# EVK-IRIS-W1-PowerSchDoc.net
KiCad netlist of a schematic drawn in Altium Designer
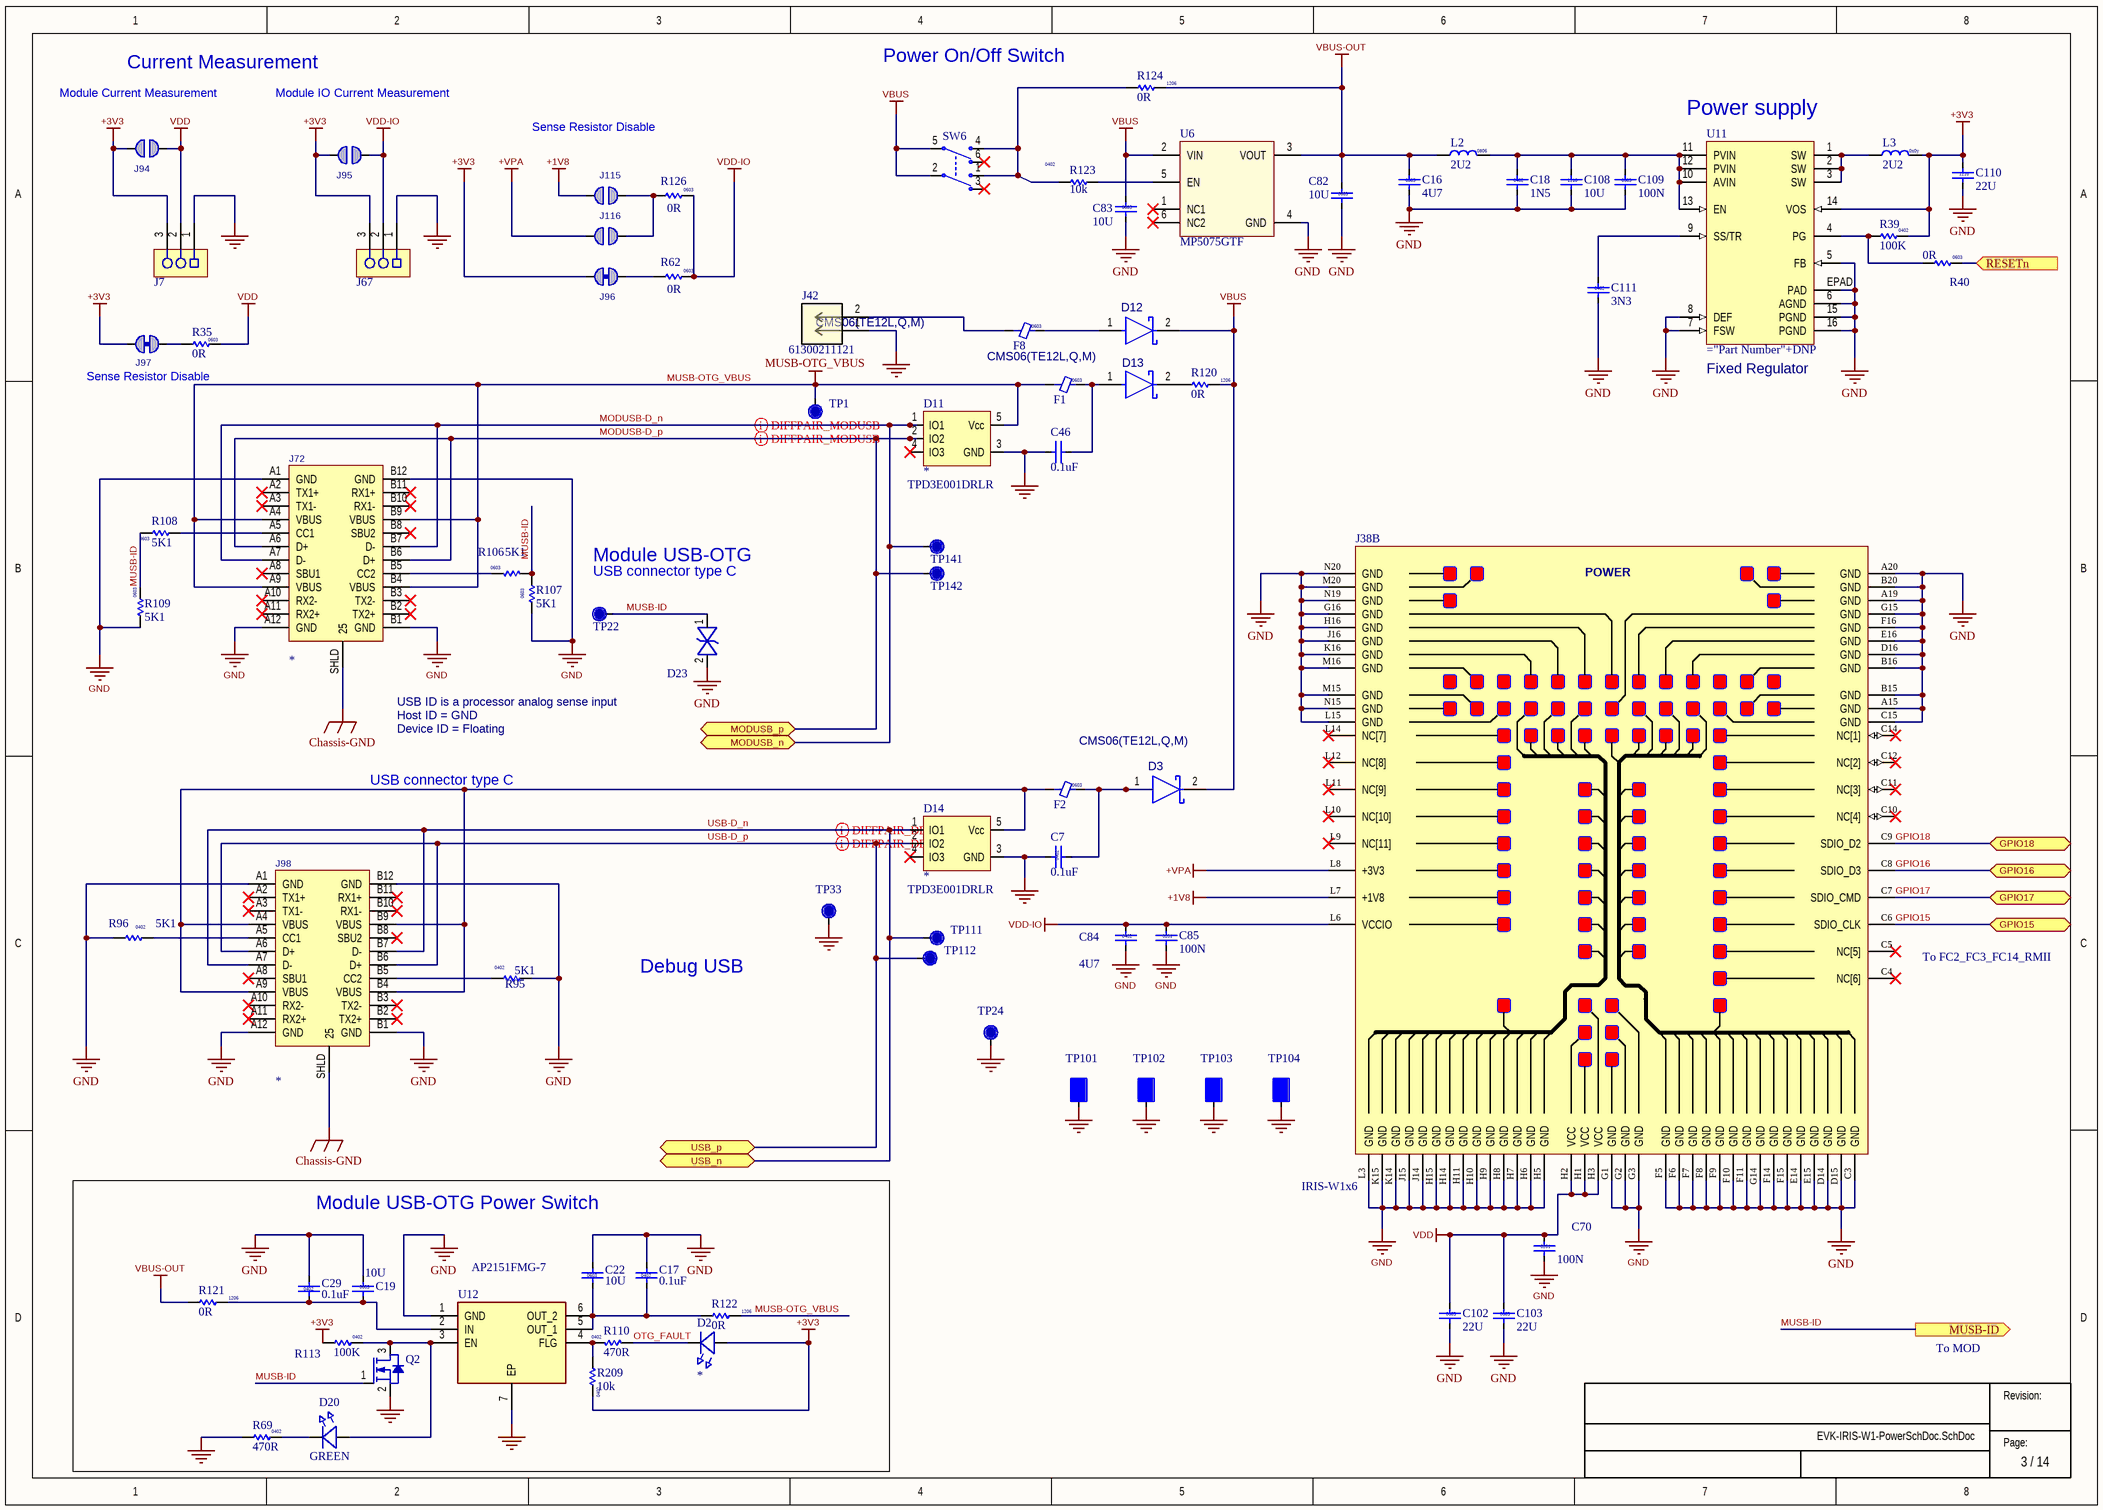
[diagram p0: EVK-IRIS-W1-PowerSchDoc.SchDoc]

(export (version "E")
  (design (tool "Eeschema 10.0.6"))
  (components
    (comp (ref "C7")
      (value "0.1uF")
      (footprint "Cap 0402 HD")
      (description "Cap, Ceramic 0.1uF 10V 10% X5R 0402")
      (fields
        (field (name "SIZE") "0402")
        (field (name "PART NUMBER") "120-00016")
        (field (name "TOLERANCE") "+/- 10%")
      )
      (libsource (lib "Arena_Parts_DB_Lib") (part "Cap Chip"))
    )
    (comp (ref "C16")
      (value "4U7")
      (footprint "Cap 0805")
      (description "CAP CER X5R 0805 4U7 10% 25V")
      (fields
        (field (name "SIZE") "0805")
        (field (name "PART NUMBER") "UBXH01-0000007")
        (field (name "TOLERANCE") "10%")
      )
      (libsource (lib "UBX_Parts_DB_Lib") (part "Cap Chip"))
    )
    (comp (ref "C17")
      (value "0.1uF")
      (footprint "Cap 0402 HD")
      (description "Cap, Ceramic 0.1uF 10V 10% X5R 0402")
      (fields
        (field (name "SIZE") "0402")
        (field (name "PART NUMBER") "120-00016")
        (field (name "TOLERANCE") "+/- 10%")
      )
      (libsource (lib "Arena_Parts_DB_Lib") (part "Cap Chip"))
    )
    (comp (ref "C18")
      (value "1N5")
      (footprint "CAP 0402")
      (description "CAP CER X7R 0402 1N5 10% 50V")
      (fields
        (field (name "SIZE") "0402")
        (field (name "PART NUMBER") "UBXH01-0000211")
        (field (name "TOLERANCE") "10%")
      )
      (libsource (lib "UBX_Parts_DB_Lib") (part "Cap Chip"))
    )
    (comp (ref "C19")
      (value "10U")
      (footprint "Cap 0603 HD")
      (description "CAP CER X7R 0603 10U 20% 10V")
      (fields
        (field (name "SIZE") "0603")
        (field (name "PART NUMBER") "UBXH01-0000310")
        (field (name "TOLERANCE") "20%")
      )
      (libsource (lib "UBX_Parts_DB_Lib") (part "Cap Chip"))
    )
    (comp (ref "C22")
      (value "10U")
      (footprint "Cap 0603 HD")
      (description "CAP CER X7R 0603 10U 20% 10V")
      (fields
        (field (name "SIZE") "0603")
        (field (name "PART NUMBER") "UBXH01-0000310")
        (field (name "TOLERANCE") "20%")
      )
      (libsource (lib "UBX_Parts_DB_Lib") (part "Cap Chip"))
    )
    (comp (ref "C29")
      (value "0.1uF")
      (footprint "Cap 0402 HD")
      (description "Cap, Ceramic 0.1uF 10V 10% X5R 0402")
      (fields
        (field (name "SIZE") "0402")
        (field (name "PART NUMBER") "120-00016")
        (field (name "TOLERANCE") "+/- 10%")
      )
      (libsource (lib "Arena_Parts_DB_Lib") (part "Cap Chip"))
    )
    (comp (ref "C46")
      (value "0.1uF")
      (footprint "Cap 0402 HD")
      (description "Cap, Ceramic 0.1uF 10V 10% X5R 0402")
      (fields (field (name "PART NUMBER") "120-00016") (field (name "TOLERANCE") "+/- 10%"))
      (libsource (lib "Arena_Parts_DB_Lib") (part "Cap Chip"))
    )
    (comp (ref "C70")
      (value "100N")
      (footprint "Cap 0201 HD")
      (description "CAP CER X5R 0201 100N 10% 10V")
      (fields
        (field (name "SIZE") "0201")
        (field (name "PART NUMBER") "UBXH01-0000245")
        (field (name "TOLERANCE") "10%")
      )
      (libsource (lib "UBX_Parts_DB_Lib") (part "Cap Chip"))
    )
    (comp (ref "C82")
      (value "10U")
      (footprint "Cap 0603 HD")
      (description "CAP CER X7R 0603 10U 20% 10V")
      (fields
        (field (name "SIZE") "0603")
        (field (name "PART NUMBER") "UBXH01-0000310")
        (field (name "TOLERANCE") "20%")
      )
      (libsource (lib "UBX_Parts_DB_Lib") (part "Cap Chip"))
    )
    (comp (ref "C83")
      (value "10U")
      (footprint "Cap 0603 HD")
      (description "CAP CER X7R 0603 10U 20% 10V")
      (fields
        (field (name "SIZE") "0603")
        (field (name "PART NUMBER") "UBXH01-0000310")
        (field (name "TOLERANCE") "20%")
      )
      (libsource (lib "UBX_Parts_DB_Lib") (part "Cap Chip"))
    )
    (comp (ref "C84")
      (value "4U7")
      (footprint "Cap 0402 HD")
      (description "CAP CER X5R 0402 4U7 20% 10V")
      (fields
        (field (name "SIZE") "0402")
        (field (name "PART NUMBER") "UBXH01-0000243")
        (field (name "TOLERANCE") "20%")
      )
      (libsource (lib "UBX_Parts_DB_Lib") (part "Cap Chip"))
    )
    (comp (ref "C85")
      (value "100N")
      (footprint "Cap 0201 HD")
      (description "CAP CER X5R 0201 100N 10% 10V")
      (fields
        (field (name "SIZE") "0201")
        (field (name "PART NUMBER") "UBXH01-0000245")
        (field (name "TOLERANCE") "10%")
      )
      (libsource (lib "UBX_Parts_DB_Lib") (part "Cap Chip"))
    )
    (comp (ref "C102")
      (value "22U")
      (footprint "Cap 0603")
      (description "CAP CER X5R 0603 22U 20% 10V")
      (fields
        (field (name "SIZE") "0603")
        (field (name "PART NUMBER") "UBXH01-0000150")
        (field (name "TOLERANCE") "20%")
      )
      (libsource (lib "UBX_Parts_DB_Lib") (part "Cap Chip"))
    )
    (comp (ref "C103")
      (value "22U")
      (footprint "Cap 0603")
      (description "CAP CER X5R 0603 22U 20% 10V")
      (fields
        (field (name "SIZE") "0603")
        (field (name "PART NUMBER") "UBXH01-0000150")
        (field (name "TOLERANCE") "20%")
      )
      (libsource (lib "UBX_Parts_DB_Lib") (part "Cap Chip"))
    )
    (comp (ref "C108")
      (value "10U")
      (footprint "Cap 1210")
      (description "CAP CER X5R 1210 10U 10% 25V")
      (fields
        (field (name "SIZE") "1210")
        (field (name "PART NUMBER") "UBXH01-3001004")
        (field (name "TOLERANCE") "10%")
      )
      (libsource (lib "UBX_Parts_DB_Lib") (part "Cap Chip"))
    )
    (comp (ref "C109")
      (value "100N")
      (footprint "Cap 0603 HD")
      (description "CAP CER X7R 0603 100N 10% 25V")
      (fields
        (field (name "SIZE") "0603")
        (field (name "PART NUMBER") "UBXH01-0047032")
        (field (name "TOLERANCE") "10%")
      )
      (libsource (lib "UBX_Parts_DB_Lib") (part "Cap Chip"))
    )
    (comp (ref "C110")
      (value "22U")
      (footprint "Cap 1210")
      (description "CAP CER X5R 1210 22U 10% 25V")
      (fields
        (field (name "SIZE") "1210")
        (field (name "PART NUMBER") "UBXH01-3001005")
        (field (name "TOLERANCE") "10%")
      )
      (libsource (lib "UBX_Parts_DB_Lib") (part "Cap Chip"))
    )
    (comp (ref "C111")
      (value "3N3")
      (footprint "CAP 0402")
      (description "CAP CER X7R 0402 3N3 10% 16V")
      (fields
        (field (name "SIZE") "0402")
        (field (name "PART NUMBER") "UBXH01-0023019")
        (field (name "TOLERANCE") "10%")
      )
      (libsource (lib "UBX_Parts_DB_Lib") (part "Cap Chip"))
    )
    (comp (ref "D2")
      (value "UBXH11-5006003")
      (footprint "LED-0603")
      (description "LED CHIP 0603 LOW CURRENT VISHAY RED 2mA")
      (fields (field (name "COLOR") "*") (field (name "MANUFACTURER") "Vishay"))
      (libsource (lib "UBX_Parts_DB_Lib") (part "LED_BASE"))
    )
    (comp (ref "D3")
      (value "CMS06(TE12L,Q,M)")
      (footprint "FP-M-FLAT-MFG")
      (description "DIODE SCHOTTKY 30V 2A MFLAT")
      (fields (field (name "MANUFACTURER") "TOSHIBA"))
      (libsource (lib "CMS06(TE12L,Q,M)") (part "360ad2f4ac25a952324d13796385471"))
    )
    (comp (ref "D11")
      (value "110-00018")
      (footprint "SOT-553")
      (description "TVS Diode, ESD High Speed 3-Channel Array, SOT-553")
      (fields
        (field (name "MANUFACTURER P/N") "*")
        (field (name "MANUFACTURER PART NUMBER 1") "TPD3E001DRLR")
        (field (name "VOLTAGE") "5.5V")
      )
      (libsource (lib "Arena_Parts_DB_Lib") (part "TPD3E001"))
    )
    (comp (ref "D12")
      (value "CMS06(TE12L,Q,M)")
      (footprint "FP-M-FLAT-MFG")
      (description "Diode Schottky 30 V 2A Surface Mount M-FLAT (2.4x3.8)")
      (fields (field (name "MANUFACTURER") "Toshiba"))
      (libsource (lib "CMS06(TE12L,Q,M)") (part "360ad2f4ac25a952324d13796385471"))
    )
    (comp (ref "D13")
      (value "CMS06(TE12L,Q,M)")
      (footprint "FP-M-FLAT-MFG")
      (description "Diode Schottky 30 V 2A Surface Mount M-FLAT (2.4x3.8)")
      (fields (field (name "MANUFACTURER") "TOSHIBA"))
      (libsource (lib "CMS06(TE12L,Q,M)") (part "360ad2f4ac25a952324d13796385471"))
    )
    (comp (ref "D14")
      (value "110-00018")
      (footprint "SOT-553")
      (description "TVS Diode, ESD High Speed 3-Channel Array, SOT-553")
      (fields
        (field (name "MANUFACTURER P/N") "*")
        (field (name "MANUFACTURER PART NUMBER 1") "TPD3E001DRLR")
        (field (name "VOLTAGE") "5.5V")
      )
      (libsource (lib "Arena_Parts_DB_Lib") (part "TPD3E001"))
    )
    (comp (ref "D20")
      (value "GREEN")
      (footprint "LED-0603")
      (description "LED CHIP 0603 LOW CURRENT OSRAM 0.002A GREEN 2.2V 2mA")
      (fields (field (name "PART NUMBER") "UBXH11-0000018") (field (name "MANUFACTURER") "Osram"))
      (libsource (lib "UBX_Parts_DB_Lib") (part "LED_BASE"))
    )
    (comp (ref "D23")
      (value "110-00019")
      (footprint "SOD-923")
      (description "Diode, ESD9B, 3.3V, ST5G, SOD-923")
      (fields (field (name "VOLTAGE") "3.3V"))
      (libsource (lib "Arena_Parts_DB_Lib") (part "Diode_TVS"))
    )
    (comp (ref "F1")
      (value "UBXH08-0000038")
      (footprint "IND 0603")
      (description "FERRITE BEAD MURATA BLM18PG 0603 120R@100MHZ 2A")
      (fields (field (name "SIZE") "0603") (field (name "MANUFACTURER") "Murata Manufacturing Company, Ltd."))
      (libsource (lib "UBX_Parts_DB_Lib") (part "FB sm"))
    )
    (comp (ref "F2")
      (value "UBXH08-0000038")
      (footprint "IND 0603")
      (description "FERRITE BEAD MURATA BLM18PG 0603 120R@100MHZ 2A")
      (fields (field (name "SIZE") "0603") (field (name "MANUFACTURER") "Murata Manufacturing Company, Ltd."))
      (libsource (lib "UBX_Parts_DB_Lib") (part "FB sm"))
    )
    (comp (ref "F8")
      (value "UBXH08-0000038")
      (footprint "IND 0603")
      (description "FERRITE BEAD MURATA BLM18PG 0603 120R@100MHZ 2A")
      (fields (field (name "SIZE") "0603") (field (name "MANUFACTURER") "Murata Manufacturing Company, Ltd."))
      (libsource (lib "UBX_Parts_DB_Lib") (part "FB sm"))
    )
    (comp (ref "J7")
      (value "130-00105")
      (footprint "HDR-0.1P-3Pin-1Row-SMT")
      (description "Header, 0.100\" Pitch, 3 Pin, Vertical SMT, Black")
      (fields (field (name "VOLTAGE") "None"))
      (libsource (lib "Arena_Parts_DB_Lib") (part "CON-3Pin_1Row"))
    )
    (comp (ref "J38")
      (value "IRIS-W1x6")
      (footprint "IRIS-W1x6_LGA152")
      (description "SHORT RANGE STAND-ALONE MULTIRADIO MODULE U-BLOX IRIS-W106")
      (fields (field (name "PART NUMBER") "UBXH14-0000681"))
      (libsource (lib "UBX_Parts_DB_Lib") (part "IRIS-W1_152pin"))
    )
    (comp (ref "J42")
      (value "61300211121")
      (footprint "CONN_61300211121_WRE")
      (description "No Description Available")
      (libsource (lib "61300211121") (part "61300211121"))
    )
    (comp (ref "J67")
      (value "130-00105")
      (footprint "HDR-0.1P-3Pin-1Row-SMT")
      (description "Header, 0.100\" Pitch, 3 Pin, Vertical SMT, Black")
      (fields (field (name "VOLTAGE") "None"))
      (libsource (lib "Arena_Parts_DB_Lib") (part "CON-3Pin_1Row"))
    )
    (comp (ref "J72")
      (value "130-00150")
      (footprint "CON_USB-C-RA_W-6Tabs")
      (description "Connector, USB-C Receptacle, 24 Position, Surface Mount, Right Angle, Horizontal, 20V")
      (fields (field (name "MANUFACTURER P/N") "*") (field (name "VOLTAGE") "20V"))
      (libsource (lib "Arena_Parts_DB_Lib") (part "USB-24Pin_W-Shield"))
    )
    (comp (ref "J94")
      (value "Solderbridge-OpenDNP")
      (footprint "Solderbridge-Open")
      (description "Solderbridge-Open")
      (libsource (lib "PCB_Misc") (part "Solderbridge-Open"))
    )
    (comp (ref "J95")
      (value "Solderbridge-OpenDNP")
      (footprint "Solderbridge-Open")
      (description "Solderbridge-Open")
      (libsource (lib "PCB_Misc") (part "Solderbridge-Open"))
    )
    (comp (ref "J96")
      (value "Solderbridge-ShortDNP")
      (footprint "Solderbridge-Short")
      (description "Solderbridge-Short")
      (libsource (lib "PCB_Misc") (part "Solderbridge-Short"))
    )
    (comp (ref "J97")
      (value "Solderbridge-ShortDNP")
      (footprint "Solderbridge-Short")
      (description "Solderbridge-Short")
      (libsource (lib "PCB_Misc") (part "Solderbridge-Short"))
    )
    (comp (ref "J98")
      (value "130-00150")
      (footprint "CON_USB-C-RA_W-6Tabs")
      (description "Connector, USB-C Receptacle, 24 Position, Surface Mount, Right Angle, Horizontal, 20V")
      (fields (field (name "MANUFACTURER P/N") "*") (field (name "VOLTAGE") "20V"))
      (libsource (lib "Arena_Parts_DB_Lib") (part "USB-24Pin_W-Shield"))
    )
    (comp (ref "J115")
      (value "Solderbridge-OpenDNP")
      (footprint "Solderbridge-Open")
      (description "Solderbridge-Open")
      (libsource (lib "PCB_Misc") (part "Solderbridge-Open"))
    )
    (comp (ref "J116")
      (value "Solderbridge-OpenDNP")
      (footprint "Solderbridge-Open")
      (description "Solderbridge-Open")
      (libsource (lib "PCB_Misc") (part "Solderbridge-Open"))
    )
    (comp (ref "L2")
      (value "2U2")
      (footprint "IND 0806")
      (description "IND MURATA LQM2MP 0806 2U2 30% 1.2A")
      (fields
        (field (name "SIZE") "0806")
        (field (name "PART NUMBER") "UBXH09-0000025")
        (field (name "TOLERANCE") "30%")
      )
      (libsource (lib "UBX_Parts_DB_Lib") (part "Ind sm"))
    )
    (comp (ref "L3")
      (value "2U2")
      (footprint "Ind_4mmx4mm")
      (description "SHIELDED POWER INDUCTOR XFL4020 2U2 20% 3.1A")
      (fields
        (field (name "SIZE") "0x0y")
        (field (name "PART NUMBER") "UBXH09-0000176")
        (field (name "TOLERANCE") "20%")
      )
      (libsource (lib "UBX_Parts_DB_Lib") (part "Ind sm"))
    )
    (comp (ref "Q2")
      (value "140-00017")
      (footprint "SOT-323")
      (description "N-MOSFET, 60V, 310mA, SOT-323-3")
      (fields (field (name "VOLTAGE") "60V"))
      (libsource (lib "Arena_Parts_DB_Lib") (part "MOSFET-N"))
    )
    (comp (ref "R35")
      (value "0R")
      (footprint "RES 0603 HD")
      (description "RES THICK FILM CHIP 0603 0R 0 100mW")
      (fields
        (field (name "SIZE") "0603")
        (field (name "PART NUMBER") "UBXH18-0003001")
        (field (name "TOLERANCE") "0")
      )
      (libsource (lib "UBX_Parts_DB_Lib") (part "Res sm"))
    )
    (comp (ref "R39")
      (value "100K")
      (footprint "RES 0402 HD")
      (description "RES THICK FILM CHIP 0402 100K 1% 63mW")
      (fields
        (field (name "SIZE") "0402")
        (field (name "PART NUMBER") "UBXH18-0000005")
        (field (name "TOLERANCE") "1%")
      )
      (libsource (lib "UBX_Parts_DB_Lib") (part "Res sm"))
    )
    (comp (ref "R40")
      (value "0R")
      (footprint "RES 0603 HD")
      (description "RES THICK FILM CHIP 0603 0R 0 100mW")
      (fields
        (field (name "SIZE") "0603")
        (field (name "PART NUMBER") "UBXH18-0003001")
        (field (name "TOLERANCE") "0")
      )
      (libsource (lib "UBX_Parts_DB_Lib") (part "Res sm"))
    )
    (comp (ref "R62")
      (value "0R")
      (footprint "RES 0603 HD")
      (description "RES THICK FILM CHIP 0603 0R 0 100mW")
      (fields
        (field (name "SIZE") "0603")
        (field (name "PART NUMBER") "UBXH18-0003001")
        (field (name "TOLERANCE") "0")
      )
      (libsource (lib "UBX_Parts_DB_Lib") (part "Res sm"))
    )
    (comp (ref "R69")
      (value "470R")
      (footprint "RES 0402 HD")
      (description "RES THICK FILM CHIP 0402 470R 5% 100mW")
      (fields
        (field (name "SIZE") "0402")
        (field (name "PART NUMBER") "UBXH18-0008041")
        (field (name "TOLERANCE") "5%")
      )
      (libsource (lib "UBX_Parts_DB_Lib") (part "Res sm"))
    )
    (comp (ref "R95")
      (value "5K1")
      (footprint "RES 0402 HD")
      (description "RES THICK FILM CHIP 0402 5K1 5% 100mW")
      (fields
        (field (name "SIZE") "0402")
        (field (name "PART NUMBER") "UBXH18-0008066")
        (field (name "TOLERANCE") "5%")
      )
      (libsource (lib "UBX_Parts_DB_Lib") (part "Res sm"))
    )
    (comp (ref "R96")
      (value "5K1")
      (footprint "RES 0402 HD")
      (description "RES THICK FILM CHIP 0402 5K1 5% 100mW")
      (fields
        (field (name "SIZE") "0402")
        (field (name "PART NUMBER") "UBXH18-0008066")
        (field (name "TOLERANCE") "5%")
      )
      (libsource (lib "UBX_Parts_DB_Lib") (part "Res sm"))
    )
    (comp (ref "R106")
      (value "5K1")
      (footprint "RES 0603 HD")
      (description "RES THICK FILM CHIP 0603 100PPM TEMP 5K1 1% 75V 100mW")
      (fields
        (field (name "SIZE") "0603")
        (field (name "PART NUMBER") "UBXH18-0000010")
        (field (name "TOLERANCE") "1%")
      )
      (libsource (lib "UBX_Parts_DB_Lib") (part "Res sm"))
    )
    (comp (ref "R107")
      (value "5K1")
      (footprint "RES 0603 HD")
      (description "RES THICK FILM CHIP 0603 100PPM TEMP 5K1 1% 75V 100mW")
      (fields
        (field (name "SIZE") "0603")
        (field (name "PART NUMBER") "UBXH18-0000010")
        (field (name "TOLERANCE") "1%")
      )
      (libsource (lib "UBX_Parts_DB_Lib") (part "Res sm"))
    )
    (comp (ref "R108")
      (value "5K1")
      (footprint "RES 0603 HD")
      (description "RES THICK FILM CHIP 0603 100PPM TEMP 5K1 1% 75V 100mW")
      (fields
        (field (name "SIZE") "0603")
        (field (name "PART NUMBER") "UBXH18-0000010")
        (field (name "TOLERANCE") "1%")
      )
      (libsource (lib "UBX_Parts_DB_Lib") (part "Res sm"))
    )
    (comp (ref "R109")
      (value "5K1")
      (footprint "RES 0603 HD")
      (description "RES THICK FILM CHIP 0603 100PPM TEMP 5K1 1% 75V 100mW")
      (fields
        (field (name "SIZE") "0603")
        (field (name "PART NUMBER") "UBXH18-0000010")
        (field (name "TOLERANCE") "1%")
      )
      (libsource (lib "UBX_Parts_DB_Lib") (part "Res sm"))
    )
    (comp (ref "R110")
      (value "470R")
      (footprint "RES 0402 HD")
      (description "RES THICK FILM CHIP 0402 470R 5% 100mW")
      (fields
        (field (name "SIZE") "0402")
        (field (name "PART NUMBER") "UBXH18-0008041")
        (field (name "TOLERANCE") "5%")
      )
      (libsource (lib "UBX_Parts_DB_Lib") (part "Res sm"))
    )
    (comp (ref "R113")
      (value "100K")
      (footprint "RES 0402 HD")
      (description "RES THICK FILM CHIP 0402 100K 1% 63mW")
      (fields
        (field (name "SIZE") "0402")
        (field (name "PART NUMBER") "UBXH18-0000005")
        (field (name "TOLERANCE") "1%")
      )
      (libsource (lib "UBX_Parts_DB_Lib") (part "Res sm"))
    )
    (comp (ref "R120")
      (value "0R")
      (footprint "RES 1206")
      (description "RES THICK FILM CHIP 1206 0R 0 2A")
      (fields
        (field (name "SIZE") "1206")
        (field (name "PART NUMBER") "UBXH18-0000020")
        (field (name "TOLERANCE") "0")
      )
      (libsource (lib "UBX_Parts_DB_Lib") (part "Res sm"))
    )
    (comp (ref "R121")
      (value "0R")
      (footprint "RES 1206")
      (description "RES THICK FILM CHIP 1206 0R 0 2A")
      (fields
        (field (name "SIZE") "1206")
        (field (name "PART NUMBER") "UBXH18-0000020")
        (field (name "TOLERANCE") "0")
      )
      (libsource (lib "UBX_Parts_DB_Lib") (part "Res sm"))
    )
    (comp (ref "R122")
      (value "0R")
      (footprint "RES 1206")
      (description "RES THICK FILM CHIP 1206 0R 0 2A")
      (fields
        (field (name "SIZE") "1206")
        (field (name "PART NUMBER") "UBXH18-0000020")
        (field (name "TOLERANCE") "0")
      )
      (libsource (lib "UBX_Parts_DB_Lib") (part "Res sm"))
    )
    (comp (ref "R123")
      (value "10k")
      (footprint "RES 0402 HD")
      (description "Resistor 10k ohm 1% 1/16W, 0402")
      (fields
        (field (name "SIZE") "0402")
        (field (name "PART NUMBER") "180-00024")
        (field (name "POWER") "1/16W")
      )
      (libsource (lib "Arena_Parts_DB_Lib") (part "Res sm"))
    )
    (comp (ref "R124")
      (value "0R")
      (footprint "RES 1206")
      (description "RES THICK FILM CHIP 1206 0R 0 2A")
      (fields
        (field (name "SIZE") "1206")
        (field (name "PART NUMBER") "UBXH18-0000020")
        (field (name "TOLERANCE") "0")
      )
      (libsource (lib "UBX_Parts_DB_Lib") (part "Res sm"))
    )
    (comp (ref "R126")
      (value "0R")
      (footprint "RES 0603 HD")
      (description "RES THICK FILM CHIP 0603 0R 0 100mW")
      (fields
        (field (name "SIZE") "0603")
        (field (name "PART NUMBER") "UBXH18-0003001")
        (field (name "TOLERANCE") "0")
      )
      (libsource (lib "UBX_Parts_DB_Lib") (part "Res sm"))
    )
    (comp (ref "R209")
      (value "10k")
      (footprint "RES 0402 HD")
      (description "Resistor 10k ohm 1% 1/16W, 0402")
      (fields
        (field (name "SIZE") "0402")
        (field (name "PART NUMBER") "180-00024")
        (field (name "POWER") "1/16W")
      )
      (libsource (lib "Arena_Parts_DB_Lib") (part "Res sm"))
    )
    (comp (ref "SW6")
      (value "137-00006")
      (footprint "SW_Slide_DPDT_JS202011SCQN")
      (description "Switch Slide DPDT, 300mA, 6V, SMT")
      (fields (field (name "VOLTAGE") "6V"))
      (libsource (lib "Arena_Parts_DB_Lib") (part "SW_DPDT"))
    )
    (comp (ref "TP1")
      (value "TP")
      (footprint "TP10R")
      (description "Testpoint, Round 1.0mm Dia")
      (fields (field (name "PART NUMBER") "TP10R"))
      (libsource (lib "LEGACY_Rigado_AltiumLib") (part "TP_R"))
    )
    (comp (ref "TP22")
      (value "TP")
      (footprint "TP10R")
      (description "Testpoint, Round 1.0mm Dia")
      (fields (field (name "PART NUMBER") "TP10R"))
      (libsource (lib "LEGACY_Rigado_AltiumLib") (part "TP_R"))
    )
    (comp (ref "TP24")
      (value "TP")
      (footprint "TP10R")
      (description "Testpoint, Round 1.0mm Dia")
      (fields (field (name "PART NUMBER") "TP10R"))
      (libsource (lib "LEGACY_Rigado_AltiumLib") (part "TP_R"))
    )
    (comp (ref "TP33")
      (value "TP")
      (footprint "TP10R")
      (description "Testpoint, Round 1.0mm Dia")
      (fields (field (name "PART NUMBER") "TP10R"))
      (libsource (lib "LEGACY_Rigado_AltiumLib") (part "TP_R"))
    )
    (comp (ref "TP101")
      (value "TP4.5x3SqDNP")
      (footprint "TP4.5x3Sq")
      (description "Testpoint, Rectangular 4.5mm x 3mm")
      (fields (field (name "PART NUMBER") "TP4.5x3Sq"))
      (libsource (lib "LEGACY_Rigado_AltiumLib") (part "TP_Sq"))
    )
    (comp (ref "TP102")
      (value "TP4.5x3SqDNP")
      (footprint "TP4.5x3Sq")
      (description "Testpoint, Rectangular 4.5mm x 3mm")
      (fields (field (name "PART NUMBER") "TP4.5x3Sq"))
      (libsource (lib "LEGACY_Rigado_AltiumLib") (part "TP_Sq"))
    )
    (comp (ref "TP103")
      (value "TP4.5x3SqDNP")
      (footprint "TP4.5x3Sq")
      (description "Testpoint, Rectangular 4.5mm x 3mm")
      (fields (field (name "PART NUMBER") "TP4.5x3Sq"))
      (libsource (lib "LEGACY_Rigado_AltiumLib") (part "TP_Sq"))
    )
    (comp (ref "TP104")
      (value "TP4.5x3SqDNP")
      (footprint "TP4.5x3Sq")
      (description "Testpoint, Rectangular 4.5mm x 3mm")
      (fields (field (name "PART NUMBER") "TP4.5x3Sq"))
      (libsource (lib "LEGACY_Rigado_AltiumLib") (part "TP_Sq"))
    )
    (comp (ref "TP111")
      (value "TP")
      (footprint "TP10R")
      (description "Testpoint, Round 1.0mm Dia")
      (fields (field (name "PART NUMBER") "TP10R"))
      (libsource (lib "LEGACY_Rigado_AltiumLib") (part "TP_R"))
    )
    (comp (ref "TP112")
      (value "TP")
      (footprint "TP10R")
      (description "Testpoint, Round 1.0mm Dia")
      (fields (field (name "PART NUMBER") "TP10R"))
      (libsource (lib "LEGACY_Rigado_AltiumLib") (part "TP_R"))
    )
    (comp (ref "TP141")
      (value "TP")
      (footprint "TP10R")
      (description "Testpoint, Round 1.0mm Dia")
      (fields (field (name "PART NUMBER") "TP10R"))
      (libsource (lib "LEGACY_Rigado_AltiumLib") (part "TP_R"))
    )
    (comp (ref "TP142")
      (value "TP")
      (footprint "TP10R")
      (description "Testpoint, Round 1.0mm Dia")
      (fields (field (name "PART NUMBER") "TP10R"))
      (libsource (lib "LEGACY_Rigado_AltiumLib") (part "TP_R"))
    )
    (comp (ref "U6")
      (value "MP5075GTF")
      (footprint "SOT-563")
      (description "IC,MOSFET LOAD SWITCH 2.4A 3-5.5V 0.048OHM HF-ROHS")
      (fields (field (name "PART NUMBER") "265-00056") (field (name "VOLTAGE") "5.5V"))
      (libsource (lib "Arena_Parts_DB_Lib") (part "MP5075GTF"))
    )
    (comp (ref "U11")
      (value "UBXH12-0000160")
      (footprint "QFN0.5P3x3-16Pin_W-Pad")
      (description "STEP DOWN DC-DC CONVERTER 3-17V 3A TPS62132 3V3")
      (fields (field (name "MANUFACTURER") "Texas Instruments") (field (name "PARTNUMBER") "TPS62132RGTR"))
      (libsource (lib "UBX_Parts_DB_Lib") (part "TPS6213x"))
    )
    (comp (ref "U12")
      (value "AP2151FMG-7")
      (footprint "SamacSys:SON50P201X181X60-7N")
      (description "Integrated Circuit")
      (fields (field (name "MOUSER PART NUMBER") "621-AP2151FMG-7"))
      (libsource (lib "SamacSys") (part "AP2151FMG-7"))
    )
  )
  (nets
    (net (code "1") (name "+1V8") (class "Default")
      (node (ref "J115") (pin "1") (pinfunction "1_1") (pintype "passive"))
      (node (ref "J38") (pin "L7") (pinfunction "+1V8_L7") (pintype "power_in"))
    )
    (net (code "2") (name "+3V3") (class "Default")
      (node (ref "C110") (pin "1") (pinfunction "1_1") (pintype "passive"))
      (node (ref "D2") (pin "2") (pinfunction "A_2") (pintype "passive"))
      (node (ref "J67") (pin "3") (pinfunction "3_3") (pintype "passive"))
      (node (ref "J7") (pin "3") (pinfunction "3_3") (pintype "passive"))
      (node (ref "J94") (pin "1") (pinfunction "1_1") (pintype "passive"))
      (node (ref "J95") (pin "1") (pinfunction "1_1") (pintype "passive"))
      (node (ref "J96") (pin "1") (pinfunction "1_1") (pintype "passive"))
      (node (ref "J97") (pin "1") (pinfunction "1_1") (pintype "passive"))
      (node (ref "L3") (pin "2") (pinfunction "2_2") (pintype "passive"))
      (node (ref "R113") (pin "1") (pinfunction "1_1") (pintype "passive"))
      (node (ref "R209") (pin "2") (pinfunction "2_2") (pintype "passive"))
      (node (ref "R39") (pin "2") (pinfunction "2_2") (pintype "passive"))
      (node (ref "U11") (pin "14") (pinfunction "VOS_14") (pintype "input"))
    )
    (net (code "3") (name "+VPA") (class "Default")
      (node (ref "J116") (pin "1") (pinfunction "1_1") (pintype "passive"))
      (node (ref "J38") (pin "L8") (pinfunction "+3V3_L8") (pintype "power_in"))
    )
    (net (code "4") (name "/GPIO15") (class "Default")
      (node (ref "J38") (pin "C6") (pinfunction "SDIO_CLK_C6") (pintype "passive"))
    )
    (net (code "5") (name "/GPIO16") (class "Default")
      (node (ref "J38") (pin "C8") (pinfunction "SDIO_D3_C8") (pintype "passive"))
    )
    (net (code "6") (name "/GPIO17") (class "Default")
      (node (ref "J38") (pin "C7") (pinfunction "SDIO_CMD_C7") (pintype "passive"))
    )
    (net (code "7") (name "/GPIO18") (class "Default")
      (node (ref "J38") (pin "C9") (pinfunction "SDIO_D2_C9") (pintype "passive"))
    )
    (net (code "8") (name "/MODUSB-D_n") (class "Default")
      (node (ref "D11") (pin "1") (pinfunction "IO1_1") (pintype "passive"))
      (node (ref "J72") (pin "A7") (pinfunction "D-_A7") (pintype "passive"))
      (node (ref "J72") (pin "B7") (pinfunction "D-_B7") (pintype "passive"))
      (node (ref "TP141") (pin "1") (pintype "passive"))
    )
    (net (code "9") (name "/MODUSB-D_p") (class "Default")
      (node (ref "D11") (pin "2") (pinfunction "IO2_2") (pintype "passive"))
      (node (ref "J72") (pin "A6") (pinfunction "D+_A6") (pintype "passive"))
      (node (ref "J72") (pin "B6") (pinfunction "D+_B6") (pintype "passive"))
      (node (ref "TP142") (pin "1") (pintype "passive"))
    )
    (net (code "10") (name "/MUSB-ID") (class "Default")
      (node (ref "D23") (pin "1") (pintype "passive"))
      (node (ref "Q2") (pin "1") (pinfunction "G_1") (pintype "passive"))
      (node (ref "R106") (pin "1") (pinfunction "1_1") (pintype "passive"))
      (node (ref "R107") (pin "1") (pinfunction "1_1") (pintype "passive"))
      (node (ref "R108") (pin "2") (pinfunction "2_2") (pintype "passive"))
      (node (ref "R109") (pin "2") (pinfunction "2_2") (pintype "passive"))
      (node (ref "TP22") (pin "1") (pintype "passive"))
    )
    (net (code "11") (name "/OTG_FAULT") (class "Default")
      (node (ref "D2") (pin "1") (pinfunction "C_1") (pintype "passive"))
      (node (ref "R110") (pin "1") (pinfunction "1_1") (pintype "passive"))
    )
    (net (code "12") (name "/RESETn") (class "Default")
      (node (ref "R40") (pin "2") (pinfunction "2_2") (pintype "passive"))
    )
    (net (code "13") (name "/USB-D_n") (class "Default")
      (node (ref "D14") (pin "1") (pinfunction "IO1_1") (pintype "passive"))
      (node (ref "J98") (pin "A7") (pinfunction "D-_A7") (pintype "passive"))
      (node (ref "J98") (pin "B7") (pinfunction "D-_B7") (pintype "passive"))
      (node (ref "TP111") (pin "1") (pintype "passive"))
    )
    (net (code "14") (name "/USB-D_p") (class "Default")
      (node (ref "D14") (pin "2") (pinfunction "IO2_2") (pintype "passive"))
      (node (ref "J98") (pin "A6") (pinfunction "D+_A6") (pintype "passive"))
      (node (ref "J98") (pin "B6") (pinfunction "D+_B6") (pintype "passive"))
      (node (ref "TP112") (pin "1") (pintype "passive"))
    )
    (net (code "15") (name "Chassis-GND") (class "Default")
      (node (ref "J72") (pin "SHLD") (pinfunction "25_SHLD") (pintype "passive"))
      (node (ref "J98") (pin "SHLD") (pinfunction "25_SHLD") (pintype "passive"))
    )
    (net (code "16") (name "GND") (class "Default")
      (node (ref "C102") (pin "2") (pinfunction "2_2") (pintype "passive"))
      (node (ref "C103") (pin "2") (pinfunction "2_2") (pintype "passive"))
      (node (ref "C108") (pin "2") (pinfunction "2_2") (pintype "passive"))
      (node (ref "C109") (pin "2") (pinfunction "2_2") (pintype "passive"))
      (node (ref "C110") (pin "2") (pinfunction "2_2") (pintype "passive"))
      (node (ref "C111") (pin "2") (pinfunction "2_2") (pintype "passive"))
      (node (ref "C16") (pin "2") (pinfunction "2_2") (pintype "passive"))
      (node (ref "C17") (pin "2") (pinfunction "2_2") (pintype "passive"))
      (node (ref "C18") (pin "2") (pinfunction "2_2") (pintype "passive"))
      (node (ref "C19") (pin "1") (pinfunction "1_1") (pintype "passive"))
      (node (ref "C22") (pin "1") (pinfunction "1_1") (pintype "passive"))
      (node (ref "C29") (pin "2") (pinfunction "2_2") (pintype "passive"))
      (node (ref "C46") (pin "1") (pinfunction "1_1") (pintype "passive"))
      (node (ref "C7") (pin "1") (pinfunction "1_1") (pintype "passive"))
      (node (ref "C70") (pin "2") (pinfunction "2_2") (pintype "passive"))
      (node (ref "C82") (pin "2") (pinfunction "2_2") (pintype "passive"))
      (node (ref "C83") (pin "2") (pinfunction "2_2") (pintype "passive"))
      (node (ref "C84") (pin "2") (pinfunction "2_2") (pintype "passive"))
      (node (ref "C85") (pin "2") (pinfunction "2_2") (pintype "passive"))
      (node (ref "D11") (pin "3") (pinfunction "GND_3") (pintype "power_in"))
      (node (ref "D14") (pin "3") (pinfunction "GND_3") (pintype "power_in"))
      (node (ref "D23") (pin "2") (pintype "passive"))
      (node (ref "J38") (pin "A15") (pinfunction "GND_A15") (pintype "power_in"))
      (node (ref "J38") (pin "A19") (pinfunction "GND_A19") (pintype "passive"))
      (node (ref "J38") (pin "A20") (pinfunction "GND_A20") (pintype "passive"))
      (node (ref "J38") (pin "B15") (pinfunction "GND_B15") (pintype "power_in"))
      (node (ref "J38") (pin "B16") (pinfunction "GND_B16") (pintype "power_in"))
      (node (ref "J38") (pin "B20") (pinfunction "GND_B20") (pintype "passive"))
      (node (ref "J38") (pin "C15") (pinfunction "GND_C15") (pintype "power_in"))
      (node (ref "J38") (pin "C3") (pinfunction "GND_C3") (pintype "power_in"))
      (node (ref "J38") (pin "D14") (pinfunction "GND_D14") (pintype "power_in"))
      (node (ref "J38") (pin "D15") (pinfunction "GND_D15") (pintype "power_in"))
      (node (ref "J38") (pin "D16") (pinfunction "GND_D16") (pintype "power_in"))
      (node (ref "J38") (pin "E14") (pinfunction "GND_E14") (pintype "power_in"))
      (node (ref "J38") (pin "E15") (pinfunction "GND_E15") (pintype "power_in"))
      (node (ref "J38") (pin "E16") (pinfunction "GND_E16") (pintype "power_in"))
      (node (ref "J38") (pin "F10") (pinfunction "GND_F10") (pintype "power_in"))
      (node (ref "J38") (pin "F11") (pinfunction "GND_F11") (pintype "power_in"))
      (node (ref "J38") (pin "F14") (pinfunction "GND_F14") (pintype "power_in"))
      (node (ref "J38") (pin "F15") (pinfunction "GND_F15") (pintype "power_in"))
      (node (ref "J38") (pin "F16") (pinfunction "GND_F16") (pintype "power_in"))
      (node (ref "J38") (pin "F5") (pinfunction "GND_F5") (pintype "power_in"))
      (node (ref "J38") (pin "F6") (pinfunction "GND_F6") (pintype "power_in"))
      (node (ref "J38") (pin "F7") (pinfunction "GND_F7") (pintype "power_in"))
      (node (ref "J38") (pin "F8") (pinfunction "GND_F8") (pintype "power_in"))
      (node (ref "J38") (pin "F9") (pinfunction "GND_F9") (pintype "power_in"))
      (node (ref "J38") (pin "G1") (pinfunction "GND_G1") (pintype "power_in"))
      (node (ref "J38") (pin "G14") (pinfunction "GND_G14") (pintype "power_in"))
      (node (ref "J38") (pin "G15") (pinfunction "GND_G15") (pintype "power_in"))
      (node (ref "J38") (pin "G16") (pinfunction "GND_G16") (pintype "power_in"))
      (node (ref "J38") (pin "G2") (pinfunction "GND_G2") (pintype "power_in"))
      (node (ref "J38") (pin "G3") (pinfunction "GND_G3") (pintype "power_in"))
      (node (ref "J38") (pin "H10") (pinfunction "GND_H10") (pintype "power_in"))
      (node (ref "J38") (pin "H11") (pinfunction "GND_H11") (pintype "power_in"))
      (node (ref "J38") (pin "H14") (pinfunction "GND_H14") (pintype "power_in"))
      (node (ref "J38") (pin "H15") (pinfunction "GND_H15") (pintype "power_in"))
      (node (ref "J38") (pin "H16") (pinfunction "GND_H16") (pintype "power_in"))
      (node (ref "J38") (pin "H5") (pinfunction "GND_H5") (pintype "power_in"))
      (node (ref "J38") (pin "H6") (pinfunction "GND_H6") (pintype "power_in"))
      (node (ref "J38") (pin "H7") (pinfunction "GND_H7") (pintype "power_in"))
      (node (ref "J38") (pin "H8") (pinfunction "GND_H8") (pintype "power_in"))
      (node (ref "J38") (pin "H9") (pinfunction "GND_H9") (pintype "power_in"))
      (node (ref "J38") (pin "J14") (pinfunction "GND_J14") (pintype "power_in"))
      (node (ref "J38") (pin "J15") (pinfunction "GND_J15") (pintype "power_in"))
      (node (ref "J38") (pin "J16") (pinfunction "GND_J16") (pintype "power_in"))
      (node (ref "J38") (pin "K14") (pinfunction "GND_K14") (pintype "power_in"))
      (node (ref "J38") (pin "K15") (pinfunction "GND_K15") (pintype "power_in"))
      (node (ref "J38") (pin "K16") (pinfunction "GND_K16") (pintype "power_in"))
      (node (ref "J38") (pin "L15") (pinfunction "GND_L15") (pintype "power_in"))
      (node (ref "J38") (pin "L3") (pinfunction "GND_L3") (pintype "power_in"))
      (node (ref "J38") (pin "M15") (pinfunction "GND_M15") (pintype "power_in"))
      (node (ref "J38") (pin "M16") (pinfunction "GND_M16") (pintype "power_in"))
      (node (ref "J38") (pin "M20") (pinfunction "GND_M20") (pintype "passive"))
      (node (ref "J38") (pin "N15") (pinfunction "GND_N15") (pintype "power_in"))
      (node (ref "J38") (pin "N19") (pinfunction "GND_N19") (pintype "passive"))
      (node (ref "J38") (pin "N20") (pinfunction "GND_N20") (pintype "passive"))
      (node (ref "J42") (pin "1") (pinfunction "1_1") (pintype "passive"))
      (node (ref "J67") (pin "1") (pinfunction "1_1") (pintype "passive"))
      (node (ref "J7") (pin "1") (pinfunction "1_1") (pintype "passive"))
      (node (ref "J72") (pin "A1") (pinfunction "GND_A1") (pintype "passive"))
      (node (ref "J72") (pin "A12") (pinfunction "GND_A12") (pintype "passive"))
      (node (ref "J72") (pin "B1") (pinfunction "GND_B1") (pintype "passive"))
      (node (ref "J72") (pin "B12") (pinfunction "GND_B12") (pintype "passive"))
      (node (ref "J98") (pin "A1") (pinfunction "GND_A1") (pintype "passive"))
      (node (ref "J98") (pin "A12") (pinfunction "GND_A12") (pintype "passive"))
      (node (ref "J98") (pin "B1") (pinfunction "GND_B1") (pintype "passive"))
      (node (ref "J98") (pin "B12") (pinfunction "GND_B12") (pintype "passive"))
      (node (ref "Q2") (pin "2") (pinfunction "S_2") (pintype "passive"))
      (node (ref "R107") (pin "2") (pinfunction "2_2") (pintype "passive"))
      (node (ref "R109") (pin "1") (pinfunction "1_1") (pintype "passive"))
      (node (ref "R69") (pin "1") (pinfunction "1_1") (pintype "passive"))
      (node (ref "R95") (pin "2") (pinfunction "2_2") (pintype "passive"))
      (node (ref "R96") (pin "1") (pinfunction "1_1") (pintype "passive"))
      (node (ref "TP101") (pin "1") (pintype "passive"))
      (node (ref "TP102") (pin "1") (pintype "passive"))
      (node (ref "TP103") (pin "1") (pintype "passive"))
      (node (ref "TP104") (pin "1") (pintype "passive"))
      (node (ref "TP24") (pin "1") (pintype "passive"))
      (node (ref "TP33") (pin "1") (pintype "passive"))
      (node (ref "U11") (pin "15") (pinfunction "PGND_15") (pintype "power_in"))
      (node (ref "U11") (pin "16") (pinfunction "PGND_16") (pintype "power_in"))
      (node (ref "U11") (pin "5") (pinfunction "FB_5") (pintype "input"))
      (node (ref "U11") (pin "6") (pinfunction "AGND_6") (pintype "power_in"))
      (node (ref "U11") (pin "7") (pinfunction "FSW_7") (pintype "input"))
      (node (ref "U11") (pin "8") (pinfunction "DEF_8") (pintype "input"))
      (node (ref "U11") (pin "EPAD") (pinfunction "PAD_EPAD") (pintype "power_in"))
      (node (ref "U12") (pin "1") (pinfunction "GND_1") (pintype "passive"))
      (node (ref "U12") (pin "7") (pinfunction "EP_7") (pintype "passive"))
      (node (ref "U6") (pin "4") (pinfunction "GND_4") (pintype "power_in"))
    )
    (net (code "17") (name "MUSB-OTG_VBUS") (class "Default")
      (node (ref "D11") (pin "5") (pinfunction "Vcc_5") (pintype "power_in"))
      (node (ref "F1") (pin "1") (pinfunction "1_1") (pintype "passive"))
      (node (ref "J72") (pin "A4") (pinfunction "VBUS_A4") (pintype "passive"))
      (node (ref "J72") (pin "A9") (pinfunction "VBUS_A9") (pintype "passive"))
      (node (ref "J72") (pin "B4") (pinfunction "VBUS_B4") (pintype "passive"))
      (node (ref "J72") (pin "B9") (pinfunction "VBUS_B9") (pintype "passive"))
      (node (ref "R122") (pin "2") (pinfunction "2_2") (pintype "passive"))
      (node (ref "TP1") (pin "1") (pintype "passive"))
    )
    (net (code "18") (name "Net-(D3-A)") (class "Default")
      (node (ref "C7") (pin "2") (pinfunction "2_2") (pintype "passive"))
      (node (ref "D3") (pin "1") (pinfunction "A_1") (pintype "passive"))
      (node (ref "F2") (pin "2") (pinfunction "2_2") (pintype "passive"))
    )
    (net (code "19") (name "Net-(D12-A)") (class "Default")
      (node (ref "D12") (pin "1") (pinfunction "A_1") (pintype "passive"))
      (node (ref "F8") (pin "2") (pinfunction "2_2") (pintype "passive"))
    )
    (net (code "20") (name "Net-(D13-A)") (class "Default")
      (node (ref "C46") (pin "2") (pinfunction "2_2") (pintype "passive"))
      (node (ref "D13") (pin "1") (pinfunction "A_1") (pintype "passive"))
      (node (ref "F1") (pin "2") (pinfunction "2_2") (pintype "passive"))
    )
    (net (code "21") (name "Net-(D13-C)") (class "Default")
      (node (ref "D13") (pin "2") (pinfunction "C_2") (pintype "passive"))
      (node (ref "R120") (pin "1") (pinfunction "1_1") (pintype "passive"))
    )
    (net (code "22") (name "Net-(D14-Vcc)") (class "Default")
      (node (ref "D14") (pin "5") (pinfunction "Vcc_5") (pintype "power_in"))
      (node (ref "F2") (pin "1") (pinfunction "1_1") (pintype "passive"))
      (node (ref "J98") (pin "A4") (pinfunction "VBUS_A4") (pintype "passive"))
      (node (ref "J98") (pin "A9") (pinfunction "VBUS_A9") (pintype "passive"))
      (node (ref "J98") (pin "B4") (pinfunction "VBUS_B4") (pintype "passive"))
      (node (ref "J98") (pin "B9") (pinfunction "VBUS_B9") (pintype "passive"))
    )
    (net (code "23") (name "Net-(D20-A)") (class "Default")
      (node (ref "D20") (pin "2") (pinfunction "A_2") (pintype "passive"))
      (node (ref "Q2") (pin "3") (pinfunction "D_3") (pintype "passive"))
      (node (ref "R113") (pin "2") (pinfunction "2_2") (pintype "passive"))
      (node (ref "U12") (pin "3") (pinfunction "EN_3") (pintype "passive"))
    )
    (net (code "24") (name "Net-(D20-C)") (class "Default")
      (node (ref "D20") (pin "1") (pinfunction "C_1") (pintype "passive"))
      (node (ref "R69") (pin "2") (pinfunction "2_2") (pintype "passive"))
    )
    (net (code "25") (name "Net-(F8-Pad1)") (class "Default")
      (node (ref "F8") (pin "1") (pinfunction "1_1") (pintype "passive"))
      (node (ref "J42") (pin "2") (pinfunction "2_2") (pintype "passive"))
    )
    (net (code "26") (name "Net-(J72-CC1)") (class "Default")
      (node (ref "J72") (pin "A5") (pinfunction "CC1_A5") (pintype "passive"))
      (node (ref "R108") (pin "1") (pinfunction "1_1") (pintype "passive"))
    )
    (net (code "27") (name "Net-(J72-CC2)") (class "Default")
      (node (ref "J72") (pin "B5") (pinfunction "CC2_B5") (pintype "passive"))
      (node (ref "R106") (pin "2") (pinfunction "2_2") (pintype "passive"))
    )
    (net (code "28") (name "Net-(J96-Pad2)") (class "Default")
      (node (ref "J96") (pin "2") (pinfunction "2_2") (pintype "passive"))
      (node (ref "R62") (pin "1") (pinfunction "1_1") (pintype "passive"))
    )
    (net (code "29") (name "Net-(J97-Pad2)") (class "Default")
      (node (ref "J97") (pin "2") (pinfunction "2_2") (pintype "passive"))
      (node (ref "R35") (pin "2") (pinfunction "2_2") (pintype "passive"))
    )
    (net (code "30") (name "Net-(J98-CC1)") (class "Default")
      (node (ref "J98") (pin "A5") (pinfunction "CC1_A5") (pintype "passive"))
      (node (ref "R96") (pin "2") (pinfunction "2_2") (pintype "passive"))
    )
    (net (code "31") (name "Net-(J98-CC2)") (class "Default")
      (node (ref "J98") (pin "B5") (pinfunction "CC2_B5") (pintype "passive"))
      (node (ref "R95") (pin "1") (pinfunction "1_1") (pintype "passive"))
    )
    (net (code "32") (name "Net-(J115-Pad2)") (class "Default")
      (node (ref "J115") (pin "2") (pinfunction "2_2") (pintype "passive"))
      (node (ref "J116") (pin "2") (pinfunction "2_2") (pintype "passive"))
      (node (ref "R126") (pin "1") (pinfunction "1_1") (pintype "passive"))
    )
    (net (code "33") (name "Net-(L3-Pad1)") (class "Default")
      (node (ref "L3") (pin "1") (pinfunction "1_1") (pintype "passive"))
      (node (ref "U11") (pin "1") (pinfunction "SW_1") (pintype "power_in"))
      (node (ref "U11") (pin "2") (pinfunction "SW_2") (pintype "power_in"))
      (node (ref "U11") (pin "3") (pinfunction "SW_3") (pintype "power_in"))
    )
    (net (code "34") (name "Net-(SW6-N.O-1)") (class "Default")
      (node (ref "R123") (pin "2") (pinfunction "2_2") (pintype "passive"))
      (node (ref "R124") (pin "1") (pinfunction "1_1") (pintype "passive"))
      (node (ref "SW6") (pin "1") (pinfunction "N.O-1_1") (pintype "passive"))
      (node (ref "SW6") (pin "4") (pinfunction "N.O-2_4") (pintype "passive"))
    )
    (net (code "35") (name "Net-(U6-EN)") (class "Default")
      (node (ref "R123") (pin "1") (pinfunction "1_1") (pintype "passive"))
      (node (ref "U6") (pin "5") (pinfunction "EN_5") (pintype "passive"))
    )
    (net (code "36") (name "Net-(U11-AVIN)") (class "Default")
      (node (ref "C108") (pin "1") (pinfunction "1_1") (pintype "passive"))
      (node (ref "C109") (pin "1") (pinfunction "1_1") (pintype "passive"))
      (node (ref "C18") (pin "1") (pinfunction "1_1") (pintype "passive"))
      (node (ref "L2") (pin "2") (pinfunction "2_2") (pintype "passive"))
      (node (ref "U11") (pin "10") (pinfunction "AVIN_10") (pintype "power_in"))
      (node (ref "U11") (pin "11") (pinfunction "PVIN_11") (pintype "power_in"))
      (node (ref "U11") (pin "12") (pinfunction "PVIN_12") (pintype "power_in"))
      (node (ref "U11") (pin "13") (pinfunction "EN_13") (pintype "input"))
    )
    (net (code "37") (name "Net-(U11-PG)") (class "Default")
      (node (ref "R39") (pin "1") (pinfunction "1_1") (pintype "passive"))
      (node (ref "R40") (pin "1") (pinfunction "1_1") (pintype "passive"))
      (node (ref "U11") (pin "4") (pinfunction "PG_4") (pintype "tri_state"))
    )
    (net (code "38") (name "Net-(U11-SS{slash}TR)") (class "Default")
      (node (ref "C111") (pin "1") (pinfunction "1_1") (pintype "passive"))
      (node (ref "U11") (pin "9") (pinfunction "SS/TR_9") (pintype "input"))
    )
    (net (code "39") (name "Net-(U12-FLG)") (class "Default")
      (node (ref "R110") (pin "2") (pinfunction "2_2") (pintype "passive"))
      (node (ref "R209") (pin "1") (pinfunction "1_1") (pintype "passive"))
      (node (ref "U12") (pin "4") (pinfunction "FLG_4") (pintype "passive"))
    )
    (net (code "40") (name "Net-(U12-IN)") (class "Default")
      (node (ref "C19") (pin "2") (pinfunction "2_2") (pintype "passive"))
      (node (ref "C29") (pin "1") (pinfunction "1_1") (pintype "passive"))
      (node (ref "R121") (pin "2") (pinfunction "2_2") (pintype "passive"))
      (node (ref "U12") (pin "2") (pinfunction "IN_2") (pintype "passive"))
    )
    (net (code "41") (name "Net-(U12-OUT_1)") (class "Default")
      (node (ref "C17") (pin "1") (pinfunction "1_1") (pintype "passive"))
      (node (ref "C22") (pin "2") (pinfunction "2_2") (pintype "passive"))
      (node (ref "R122") (pin "1") (pinfunction "1_1") (pintype "passive"))
      (node (ref "U12") (pin "5") (pinfunction "OUT_1_5") (pintype "passive"))
      (node (ref "U12") (pin "6") (pinfunction "OUT_2_6") (pintype "passive"))
    )
    (net (code "42") (name "VBUS") (class "Default")
      (node (ref "C83") (pin "1") (pinfunction "1_1") (pintype "passive"))
      (node (ref "D12") (pin "2") (pinfunction "C_2") (pintype "passive"))
      (node (ref "D3") (pin "2") (pinfunction "C_2") (pintype "passive"))
      (node (ref "R120") (pin "2") (pinfunction "2_2") (pintype "passive"))
      (node (ref "SW6") (pin "2") (pinfunction "COM-1_2") (pintype "passive"))
      (node (ref "SW6") (pin "5") (pinfunction "COM-2_5") (pintype "passive"))
      (node (ref "U6") (pin "2") (pinfunction "VIN_2") (pintype "power_in"))
    )
    (net (code "43") (name "VBUS-OUT") (class "Default")
      (node (ref "C16") (pin "1") (pinfunction "1_1") (pintype "passive"))
      (node (ref "C82") (pin "1") (pinfunction "1_1") (pintype "passive"))
      (node (ref "L2") (pin "1") (pinfunction "1_1") (pintype "passive"))
      (node (ref "R121") (pin "1") (pinfunction "1_1") (pintype "passive"))
      (node (ref "R124") (pin "2") (pinfunction "2_2") (pintype "passive"))
      (node (ref "U6") (pin "3") (pinfunction "VOUT_3") (pintype "power_in"))
    )
    (net (code "44") (name "VDD") (class "Default")
      (node (ref "C102") (pin "1") (pinfunction "1_1") (pintype "passive"))
      (node (ref "C103") (pin "1") (pinfunction "1_1") (pintype "passive"))
      (node (ref "C70") (pin "1") (pinfunction "1_1") (pintype "passive"))
      (node (ref "J38") (pin "H1") (pinfunction "VCC_H1") (pintype "power_in"))
      (node (ref "J38") (pin "H2") (pinfunction "VCC_H2") (pintype "power_in"))
      (node (ref "J38") (pin "H3") (pinfunction "VCC_H3") (pintype "power_in"))
      (node (ref "J7") (pin "2") (pinfunction "2_2") (pintype "passive"))
      (node (ref "J94") (pin "2") (pinfunction "2_2") (pintype "passive"))
      (node (ref "R35") (pin "1") (pinfunction "1_1") (pintype "passive"))
    )
    (net (code "45") (name "VDD-IO") (class "Default")
      (node (ref "C84") (pin "1") (pinfunction "1_1") (pintype "passive"))
      (node (ref "C85") (pin "1") (pinfunction "1_1") (pintype "passive"))
      (node (ref "J38") (pin "L6") (pinfunction "VCCIO_L6") (pintype "power_in"))
      (node (ref "J67") (pin "2") (pinfunction "2_2") (pintype "passive"))
      (node (ref "J95") (pin "2") (pinfunction "2_2") (pintype "passive"))
      (node (ref "R126") (pin "2") (pinfunction "2_2") (pintype "passive"))
      (node (ref "R62") (pin "2") (pinfunction "2_2") (pintype "passive"))
    )
    (net (code "46") (name "unconnected-(D11-IO3-Pad4)") (class "Default")
      (node (ref "D11") (pin "4") (pinfunction "IO3_4") (pintype "passive+no_connect"))
    )
    (net (code "47") (name "unconnected-(D14-IO3-Pad4)") (class "Default")
      (node (ref "D14") (pin "4") (pinfunction "IO3_4") (pintype "passive+no_connect"))
    )
    (net (code "48") (name "unconnected-(J38B-NC[1]-PadC14)") (class "Default")
      (node (ref "J38") (pin "C14") (pinfunction "NC[1]_C14") (pintype "bidirectional+no_connect"))
    )
    (net (code "49") (name "unconnected-(J38B-NC[2]-PadC12)") (class "Default")
      (node (ref "J38") (pin "C12") (pinfunction "NC[2]_C12") (pintype "bidirectional+no_connect"))
    )
    (net (code "50") (name "unconnected-(J38B-NC[3]-PadC11)") (class "Default")
      (node (ref "J38") (pin "C11") (pinfunction "NC[3]_C11") (pintype "bidirectional+no_connect"))
    )
    (net (code "51") (name "unconnected-(J38B-NC[4]-PadC10)") (class "Default")
      (node (ref "J38") (pin "C10") (pinfunction "NC[4]_C10") (pintype "bidirectional+no_connect"))
    )
    (net (code "52") (name "unconnected-(J38B-NC[5]-PadC5)") (class "Default")
      (node (ref "J38") (pin "C5") (pinfunction "NC[5]_C5") (pintype "passive+no_connect"))
    )
    (net (code "53") (name "unconnected-(J38B-NC[6]-PadC4)") (class "Default")
      (node (ref "J38") (pin "C4") (pinfunction "NC[6]_C4") (pintype "passive+no_connect"))
    )
    (net (code "54") (name "unconnected-(J38B-NC[7]-PadL14)") (class "Default")
      (node (ref "J38") (pin "L14") (pinfunction "NC[7]_L14") (pintype "passive+no_connect"))
    )
    (net (code "55") (name "unconnected-(J38B-NC[8]-PadL12)") (class "Default")
      (node (ref "J38") (pin "L12") (pinfunction "NC[8]_L12") (pintype "passive+no_connect"))
    )
    (net (code "56") (name "unconnected-(J38B-NC[9]-PadL11)") (class "Default")
      (node (ref "J38") (pin "L11") (pinfunction "NC[9]_L11") (pintype "passive+no_connect"))
    )
    (net (code "57") (name "unconnected-(J38B-NC[10]-PadL10)") (class "Default")
      (node (ref "J38") (pin "L10") (pinfunction "NC[10]_L10") (pintype "passive+no_connect"))
    )
    (net (code "58") (name "unconnected-(J38B-NC[11]-PadL9)") (class "Default")
      (node (ref "J38") (pin "L9") (pinfunction "NC[11]_L9") (pintype "passive+no_connect"))
    )
    (net (code "59") (name "unconnected-(J72-RX1+-PadB11)") (class "Default")
      (node (ref "J72") (pin "B11") (pinfunction "RX1+_B11") (pintype "passive+no_connect"))
    )
    (net (code "60") (name "unconnected-(J72-RX1--PadB10)") (class "Default")
      (node (ref "J72") (pin "B10") (pinfunction "RX1-_B10") (pintype "passive+no_connect"))
    )
    (net (code "61") (name "unconnected-(J72-RX2+-PadA11)") (class "Default")
      (node (ref "J72") (pin "A11") (pinfunction "RX2+_A11") (pintype "passive+no_connect"))
    )
    (net (code "62") (name "unconnected-(J72-RX2--PadA10)") (class "Default")
      (node (ref "J72") (pin "A10") (pinfunction "RX2-_A10") (pintype "passive+no_connect"))
    )
    (net (code "63") (name "unconnected-(J72-SBU1-PadA8)") (class "Default")
      (node (ref "J72") (pin "A8") (pinfunction "SBU1_A8") (pintype "passive+no_connect"))
    )
    (net (code "64") (name "unconnected-(J72-SBU2-PadB8)") (class "Default")
      (node (ref "J72") (pin "B8") (pinfunction "SBU2_B8") (pintype "passive+no_connect"))
    )
    (net (code "65") (name "unconnected-(J72-TX1+-PadA2)") (class "Default")
      (node (ref "J72") (pin "A2") (pinfunction "TX1+_A2") (pintype "passive+no_connect"))
    )
    (net (code "66") (name "unconnected-(J72-TX1--PadA3)") (class "Default")
      (node (ref "J72") (pin "A3") (pinfunction "TX1-_A3") (pintype "passive+no_connect"))
    )
    (net (code "67") (name "unconnected-(J72-TX2+-PadB2)") (class "Default")
      (node (ref "J72") (pin "B2") (pinfunction "TX2+_B2") (pintype "passive+no_connect"))
    )
    (net (code "68") (name "unconnected-(J72-TX2--PadB3)") (class "Default")
      (node (ref "J72") (pin "B3") (pinfunction "TX2-_B3") (pintype "passive+no_connect"))
    )
    (net (code "69") (name "unconnected-(J98-RX1+-PadB11)") (class "Default")
      (node (ref "J98") (pin "B11") (pinfunction "RX1+_B11") (pintype "passive+no_connect"))
    )
    (net (code "70") (name "unconnected-(J98-RX1--PadB10)") (class "Default")
      (node (ref "J98") (pin "B10") (pinfunction "RX1-_B10") (pintype "passive+no_connect"))
    )
    (net (code "71") (name "unconnected-(J98-RX2+-PadA11)") (class "Default")
      (node (ref "J98") (pin "A11") (pinfunction "RX2+_A11") (pintype "passive+no_connect"))
    )
    (net (code "72") (name "unconnected-(J98-RX2--PadA10)") (class "Default")
      (node (ref "J98") (pin "A10") (pinfunction "RX2-_A10") (pintype "passive+no_connect"))
    )
    (net (code "73") (name "unconnected-(J98-SBU1-PadA8)") (class "Default")
      (node (ref "J98") (pin "A8") (pinfunction "SBU1_A8") (pintype "passive+no_connect"))
    )
    (net (code "74") (name "unconnected-(J98-SBU2-PadB8)") (class "Default")
      (node (ref "J98") (pin "B8") (pinfunction "SBU2_B8") (pintype "passive+no_connect"))
    )
    (net (code "75") (name "unconnected-(J98-TX1+-PadA2)") (class "Default")
      (node (ref "J98") (pin "A2") (pinfunction "TX1+_A2") (pintype "passive+no_connect"))
    )
    (net (code "76") (name "unconnected-(J98-TX1--PadA3)") (class "Default")
      (node (ref "J98") (pin "A3") (pinfunction "TX1-_A3") (pintype "passive+no_connect"))
    )
    (net (code "77") (name "unconnected-(J98-TX2+-PadB2)") (class "Default")
      (node (ref "J98") (pin "B2") (pinfunction "TX2+_B2") (pintype "passive+no_connect"))
    )
    (net (code "78") (name "unconnected-(J98-TX2--PadB3)") (class "Default")
      (node (ref "J98") (pin "B3") (pinfunction "TX2-_B3") (pintype "passive+no_connect"))
    )
    (net (code "79") (name "unconnected-(SW6-N.C-1-Pad3)") (class "Default")
      (node (ref "SW6") (pin "3") (pinfunction "N.C-1_3") (pintype "passive+no_connect"))
    )
    (net (code "80") (name "unconnected-(SW6-N.C-2-Pad6)") (class "Default")
      (node (ref "SW6") (pin "6") (pinfunction "N.C-2_6") (pintype "passive+no_connect"))
    )
    (net (code "81") (name "unconnected-(U6-NC1-Pad1)") (class "Default")
      (node (ref "U6") (pin "1") (pinfunction "NC1_1") (pintype "passive+no_connect"))
    )
    (net (code "82") (name "unconnected-(U6-NC2-Pad6)") (class "Default")
      (node (ref "U6") (pin "6") (pinfunction "NC2_6") (pintype "passive+no_connect"))
    )
  )
)
